# VapourPhaseController.net
KiCad netlist of a schematic drawn in Altium Designer
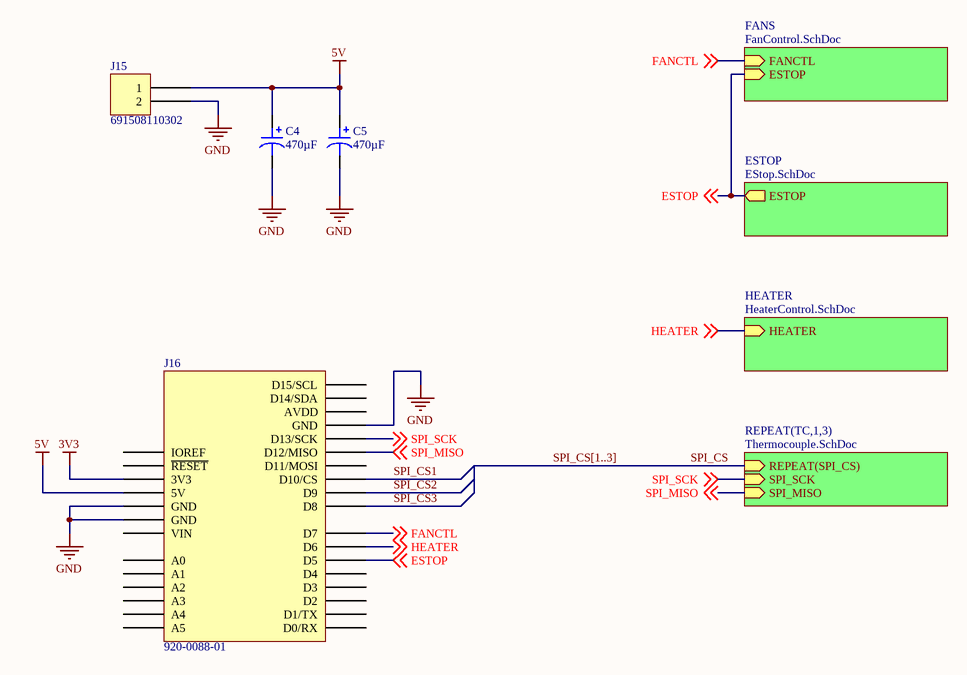
[diagram p0: VapourPhaseController.SchDoc]

(export (version "E")
  (design (tool "Eeschema 10.0.6"))
  (components
    (comp (ref "C4")
      (value "470µF")
      (footprint "CAP AL TH D8 L3.5 H12.5")
      (description "CAP ALUM 470UF 20% 16V RADIAL")
      (fields
        (field (name "PART NUMBER") "ECA-1CM471")
        (field (name "MANUFACTURER") "Panasonic Electronic Components")
      )
      (libsource (lib "Celestial Altium Library - altium_library") (part "Polarised Capacitor"))
    )
    (comp (ref "C5")
      (value "470µF")
      (footprint "CAP AL TH D8 L3.5 H12.5")
      (description "CAP ALUM 470UF 20% 16V RADIAL")
      (fields
        (field (name "PART NUMBER") "ECA-1CM471")
        (field (name "MANUFACTURER") "Panasonic Electronic Components")
      )
      (libsource (lib "Celestial Altium Library - altium_library") (part "Polarised Capacitor"))
    )
    (comp (ref "J15")
      (value "691508110302")
      (footprint "WURTH 691508110302")
      (description "TERM BLOCK 2POS 3.5MM SMD")
      (fields (field (name "MANUFACTURER") "Würth Elektronik") (field (name "VOLTAGE") "300V"))
      (libsource (lib "Celestial Altium Library - altium_library") (part "2 Pin"))
    )
    (comp (ref "J16")
      (value "920-0088-01")
      (footprint "SCHMARTBOARD - 920-0088-01")
      (description "CONN HDR 8/10P 0.1 GOLD PCB 6PC")
      (fields (field (name "MANUFACTURER") "Schmartboard, Inc."))
      (libsource (lib "Celestial Altium Library - altium_library") (part "Arduino Headers"))
    )
  )
  (nets
    (net (code "2") (name "/SPI_CS1") (class "Default")
      (node (ref "J16") (pin "25") (pinfunction "D10/CS_25") (pintype "passive"))
    )
    (net (code "3") (name "/SPI_CS2") (class "Default")
      (node (ref "J16") (pin "24") (pinfunction "D9_24") (pintype "passive"))
    )
    (net (code "4") (name "/SPI_CS3") (class "Default")
      (node (ref "J16") (pin "23") (pinfunction "D8_23") (pintype "passive"))
    )
    (net (code "6") (name "3V3") (class "Default")
      (node (ref "J16") (pin "4") (pinfunction "3V3_4") (pintype "passive"))
    )
    (net (code "7") (name "5V") (class "Default")
      (node (ref "C4") (pin "1") (pinfunction "1_1") (pintype "passive"))
      (node (ref "C5") (pin "1") (pinfunction "1_1") (pintype "passive"))
      (node (ref "J15") (pin "1") (pinfunction "1_1") (pintype "passive"))
      (node (ref "J16") (pin "5") (pinfunction "5V_5") (pintype "passive"))
    )
    (net (code "8") (name "ESTOP") (class "Default")
      (node (ref "J16") (pin "20") (pinfunction "D5_20") (pintype "passive"))
    )
    (net (code "9") (name "FANCTL") (class "Default")
      (node (ref "J16") (pin "22") (pinfunction "D7_22") (pintype "passive"))
    )
    (net (code "10") (name "GND") (class "Default")
      (node (ref "C4") (pin "2") (pinfunction "2_2") (pintype "passive"))
      (node (ref "C5") (pin "2") (pinfunction "2_2") (pintype "passive"))
      (node (ref "J15") (pin "2") (pinfunction "2_2") (pintype "passive"))
      (node (ref "J16") (pin "29") (pinfunction "GND_29") (pintype "passive"))
      (node (ref "J16") (pin "6") (pinfunction "GND_6") (pintype "passive"))
      (node (ref "J16") (pin "7") (pinfunction "GND_7") (pintype "passive"))
    )
    (net (code "11") (name "HEATER") (class "Default")
      (node (ref "J16") (pin "21") (pinfunction "D6_21") (pintype "passive"))
    )
    (net (code "12") (name "SPI_MISO") (class "Default")
      (node (ref "J16") (pin "27") (pinfunction "D12/MISO_27") (pintype "passive"))
    )
    (net (code "13") (name "SPI_SCK") (class "Default")
      (node (ref "J16") (pin "28") (pinfunction "D13/SCK_28") (pintype "passive"))
    )
    (net (code "14") (name "unconnected-(J16-A0-Pad9)") (class "Default")
      (node (ref "J16") (pin "9") (pinfunction "A0_9") (pintype "passive"))
    )
    (net (code "15") (name "unconnected-(J16-A1-Pad10)") (class "Default")
      (node (ref "J16") (pin "10") (pinfunction "A1_10") (pintype "passive"))
    )
    (net (code "16") (name "unconnected-(J16-A2-Pad11)") (class "Default")
      (node (ref "J16") (pin "11") (pinfunction "A2_11") (pintype "passive"))
    )
    (net (code "17") (name "unconnected-(J16-A3-Pad12)") (class "Default")
      (node (ref "J16") (pin "12") (pinfunction "A3_12") (pintype "passive"))
    )
    (net (code "18") (name "unconnected-(J16-A4-Pad13)") (class "Default")
      (node (ref "J16") (pin "13") (pinfunction "A4_13") (pintype "passive"))
    )
    (net (code "19") (name "unconnected-(J16-A5-Pad14)") (class "Default")
      (node (ref "J16") (pin "14") (pinfunction "A5_14") (pintype "passive"))
    )
    (net (code "20") (name "unconnected-(J16-AVDD-Pad30)") (class "Default")
      (node (ref "J16") (pin "30") (pinfunction "AVDD_30") (pintype "passive"))
    )
    (net (code "21") (name "unconnected-(J16-D0{slash}RX-Pad15)") (class "Default")
      (node (ref "J16") (pin "15") (pinfunction "D0/RX_15") (pintype "passive"))
    )
    (net (code "22") (name "unconnected-(J16-D1{slash}TX-Pad16)") (class "Default")
      (node (ref "J16") (pin "16") (pinfunction "D1/TX_16") (pintype "passive"))
    )
    (net (code "23") (name "unconnected-(J16-D2-Pad17)") (class "Default")
      (node (ref "J16") (pin "17") (pinfunction "D2_17") (pintype "passive"))
    )
    (net (code "24") (name "unconnected-(J16-D3-Pad18)") (class "Default")
      (node (ref "J16") (pin "18") (pinfunction "D3_18") (pintype "passive"))
    )
    (net (code "25") (name "unconnected-(J16-D4-Pad19)") (class "Default")
      (node (ref "J16") (pin "19") (pinfunction "D4_19") (pintype "passive"))
    )
    (net (code "26") (name "unconnected-(J16-D11{slash}MOSI-Pad26)") (class "Default")
      (node (ref "J16") (pin "26") (pinfunction "D11/MOSI_26") (pintype "passive"))
    )
    (net (code "27") (name "unconnected-(J16-D14{slash}SDA-Pad31)") (class "Default")
      (node (ref "J16") (pin "31") (pinfunction "D14/SDA_31") (pintype "passive"))
    )
    (net (code "28") (name "unconnected-(J16-D15{slash}SCL-Pad32)") (class "Default")
      (node (ref "J16") (pin "32") (pinfunction "D15/SCL_32") (pintype "passive"))
    )
    (net (code "29") (name "unconnected-(J16-IOREF-Pad2)") (class "Default")
      (node (ref "J16") (pin "2") (pinfunction "IOREF_2") (pintype "passive"))
    )
    (net (code "30") (name "unconnected-(J16-VIN-Pad8)") (class "Default")
      (node (ref "J16") (pin "8") (pinfunction "VIN_8") (pintype "passive"))
    )
    (net (code "31") (name "unconnected-(J16-~{RESET}-Pad3)") (class "Default")
      (node (ref "J16") (pin "3") (pinfunction "~{RESET}_3") (pintype "passive"))
    )
  )
)
